# RJ12Breakout4.net
KiCad netlist of a schematic drawn in EAGLE
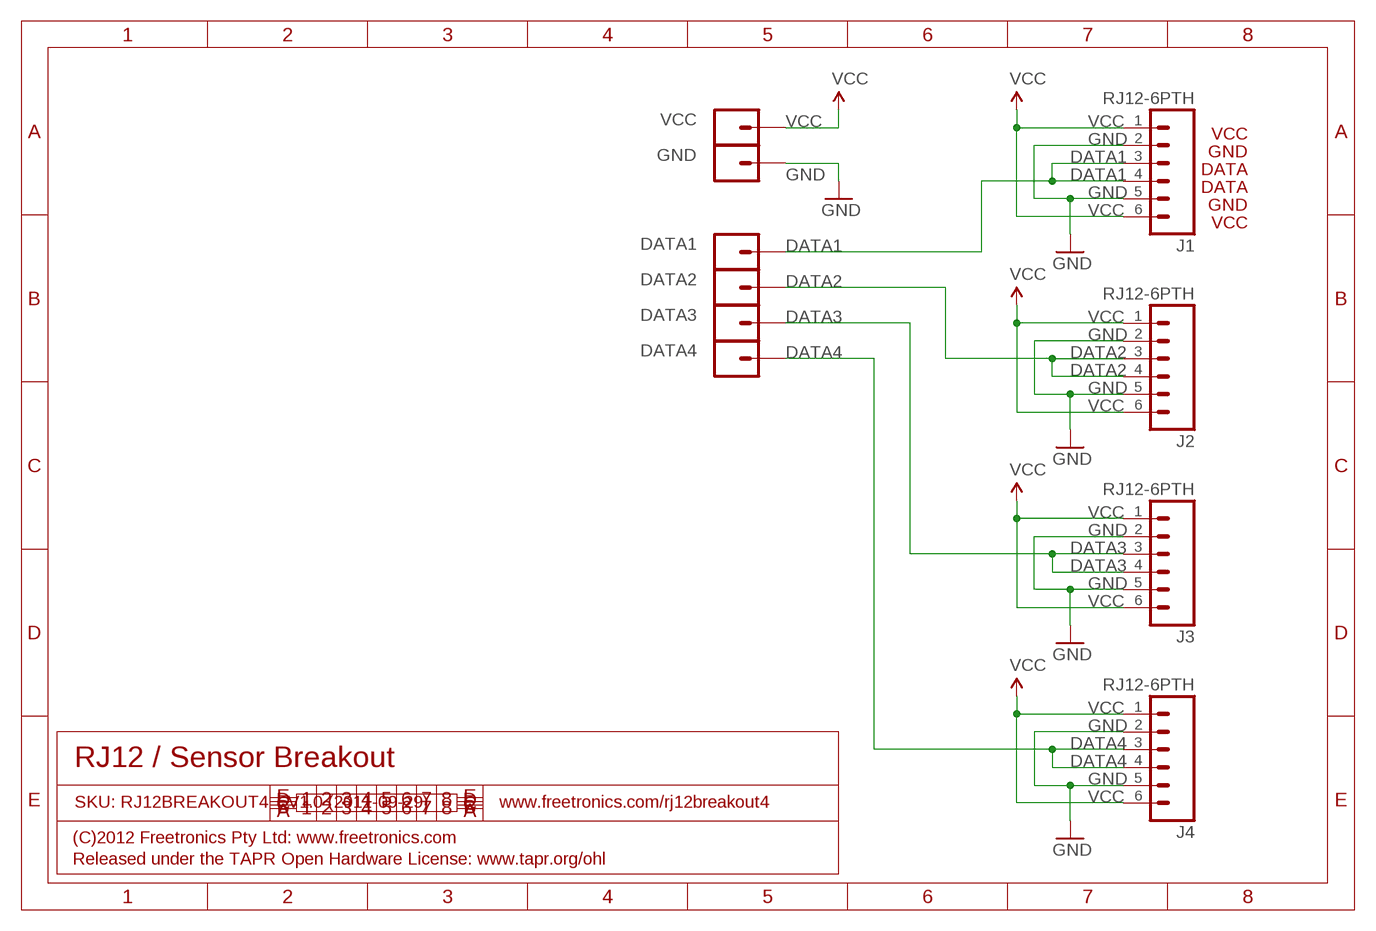
[diagram p0: schematic, sheet 1]

(export (version "E")
  (design (tool "Eeschema 10.0.6"))
  (components
    (comp (ref "DATA1")
      (value "M01PTH")
      (footprint "eagle-import:1X01")
      (libsource (lib "eagle-import") (part "M01PTH"))
    )
    (comp (ref "DATA2")
      (value "M01PTH")
      (footprint "eagle-import:1X01")
      (libsource (lib "eagle-import") (part "M01PTH"))
    )
    (comp (ref "DATA3")
      (value "M01PTH")
      (footprint "eagle-import:1X01")
      (libsource (lib "eagle-import") (part "M01PTH"))
    )
    (comp (ref "DATA4")
      (value "M01PTH")
      (footprint "eagle-import:1X01")
      (libsource (lib "eagle-import") (part "M01PTH"))
    )
    (comp (ref "GND")
      (value "M01PTH")
      (footprint "eagle-import:1X01")
      (libsource (lib "eagle-import") (part "M01PTH"))
    )
    (comp (ref "J1")
      (value "RJ12-6PTH")
      (footprint "eagle-import:RJ12-6")
      (libsource (lib "eagle-import") (part "RJ12-6PTH"))
    )
    (comp (ref "J2")
      (value "RJ12-6PTH")
      (footprint "eagle-import:RJ12-6")
      (libsource (lib "eagle-import") (part "RJ12-6PTH"))
    )
    (comp (ref "J3")
      (value "RJ12-6PTH")
      (footprint "eagle-import:RJ12-6")
      (libsource (lib "eagle-import") (part "RJ12-6PTH"))
    )
    (comp (ref "J4")
      (value "RJ12-6PTH")
      (footprint "eagle-import:RJ12-6")
      (libsource (lib "eagle-import") (part "RJ12-6PTH"))
    )
    (comp (ref "VCC")
      (value "M01PTH")
      (footprint "eagle-import:1X01")
      (libsource (lib "eagle-import") (part "M01PTH"))
    )
  )
  (nets
    (net (code "1") (name "/DATA1") (class "Default")
      (node (ref "DATA1") (pin "1") (pinfunction "1_1") (pintype "passive"))
      (node (ref "J1") (pin "3") (pinfunction "3_3") (pintype "passive"))
      (node (ref "J1") (pin "4") (pinfunction "4_4") (pintype "passive"))
    )
    (net (code "2") (name "/DATA2") (class "Default")
      (node (ref "DATA2") (pin "1") (pinfunction "1_1") (pintype "passive"))
      (node (ref "J2") (pin "3") (pinfunction "3_3") (pintype "passive"))
      (node (ref "J2") (pin "4") (pinfunction "4_4") (pintype "passive"))
    )
    (net (code "3") (name "/DATA3") (class "Default")
      (node (ref "DATA3") (pin "1") (pinfunction "1_1") (pintype "passive"))
      (node (ref "J3") (pin "3") (pinfunction "3_3") (pintype "passive"))
      (node (ref "J3") (pin "4") (pinfunction "4_4") (pintype "passive"))
    )
    (net (code "4") (name "/DATA4") (class "Default")
      (node (ref "DATA4") (pin "1") (pinfunction "1_1") (pintype "passive"))
      (node (ref "J4") (pin "3") (pinfunction "3_3") (pintype "passive"))
      (node (ref "J4") (pin "4") (pinfunction "4_4") (pintype "passive"))
    )
    (net (code "5") (name "GND") (class "Default")
      (node (ref "GND") (pin "1") (pinfunction "1_1") (pintype "passive"))
      (node (ref "J1") (pin "2") (pinfunction "2_2") (pintype "passive"))
      (node (ref "J1") (pin "5") (pinfunction "5_5") (pintype "passive"))
      (node (ref "J2") (pin "2") (pinfunction "2_2") (pintype "passive"))
      (node (ref "J2") (pin "5") (pinfunction "5_5") (pintype "passive"))
      (node (ref "J3") (pin "2") (pinfunction "2_2") (pintype "passive"))
      (node (ref "J3") (pin "5") (pinfunction "5_5") (pintype "passive"))
      (node (ref "J4") (pin "2") (pinfunction "2_2") (pintype "passive"))
      (node (ref "J4") (pin "5") (pinfunction "5_5") (pintype "passive"))
    )
    (net (code "6") (name "VCC") (class "Default")
      (node (ref "J1") (pin "1") (pinfunction "1_1") (pintype "passive"))
      (node (ref "J1") (pin "6") (pinfunction "6_6") (pintype "passive"))
      (node (ref "J2") (pin "1") (pinfunction "1_1") (pintype "passive"))
      (node (ref "J2") (pin "6") (pinfunction "6_6") (pintype "passive"))
      (node (ref "J3") (pin "1") (pinfunction "1_1") (pintype "passive"))
      (node (ref "J3") (pin "6") (pinfunction "6_6") (pintype "passive"))
      (node (ref "J4") (pin "1") (pinfunction "1_1") (pintype "passive"))
      (node (ref "J4") (pin "6") (pinfunction "6_6") (pintype "passive"))
      (node (ref "VCC") (pin "1") (pinfunction "1_1") (pintype "passive"))
    )
  )
)
